# primary_decoupling.net
KiCad netlist of a schematic drawn in Altium Designer
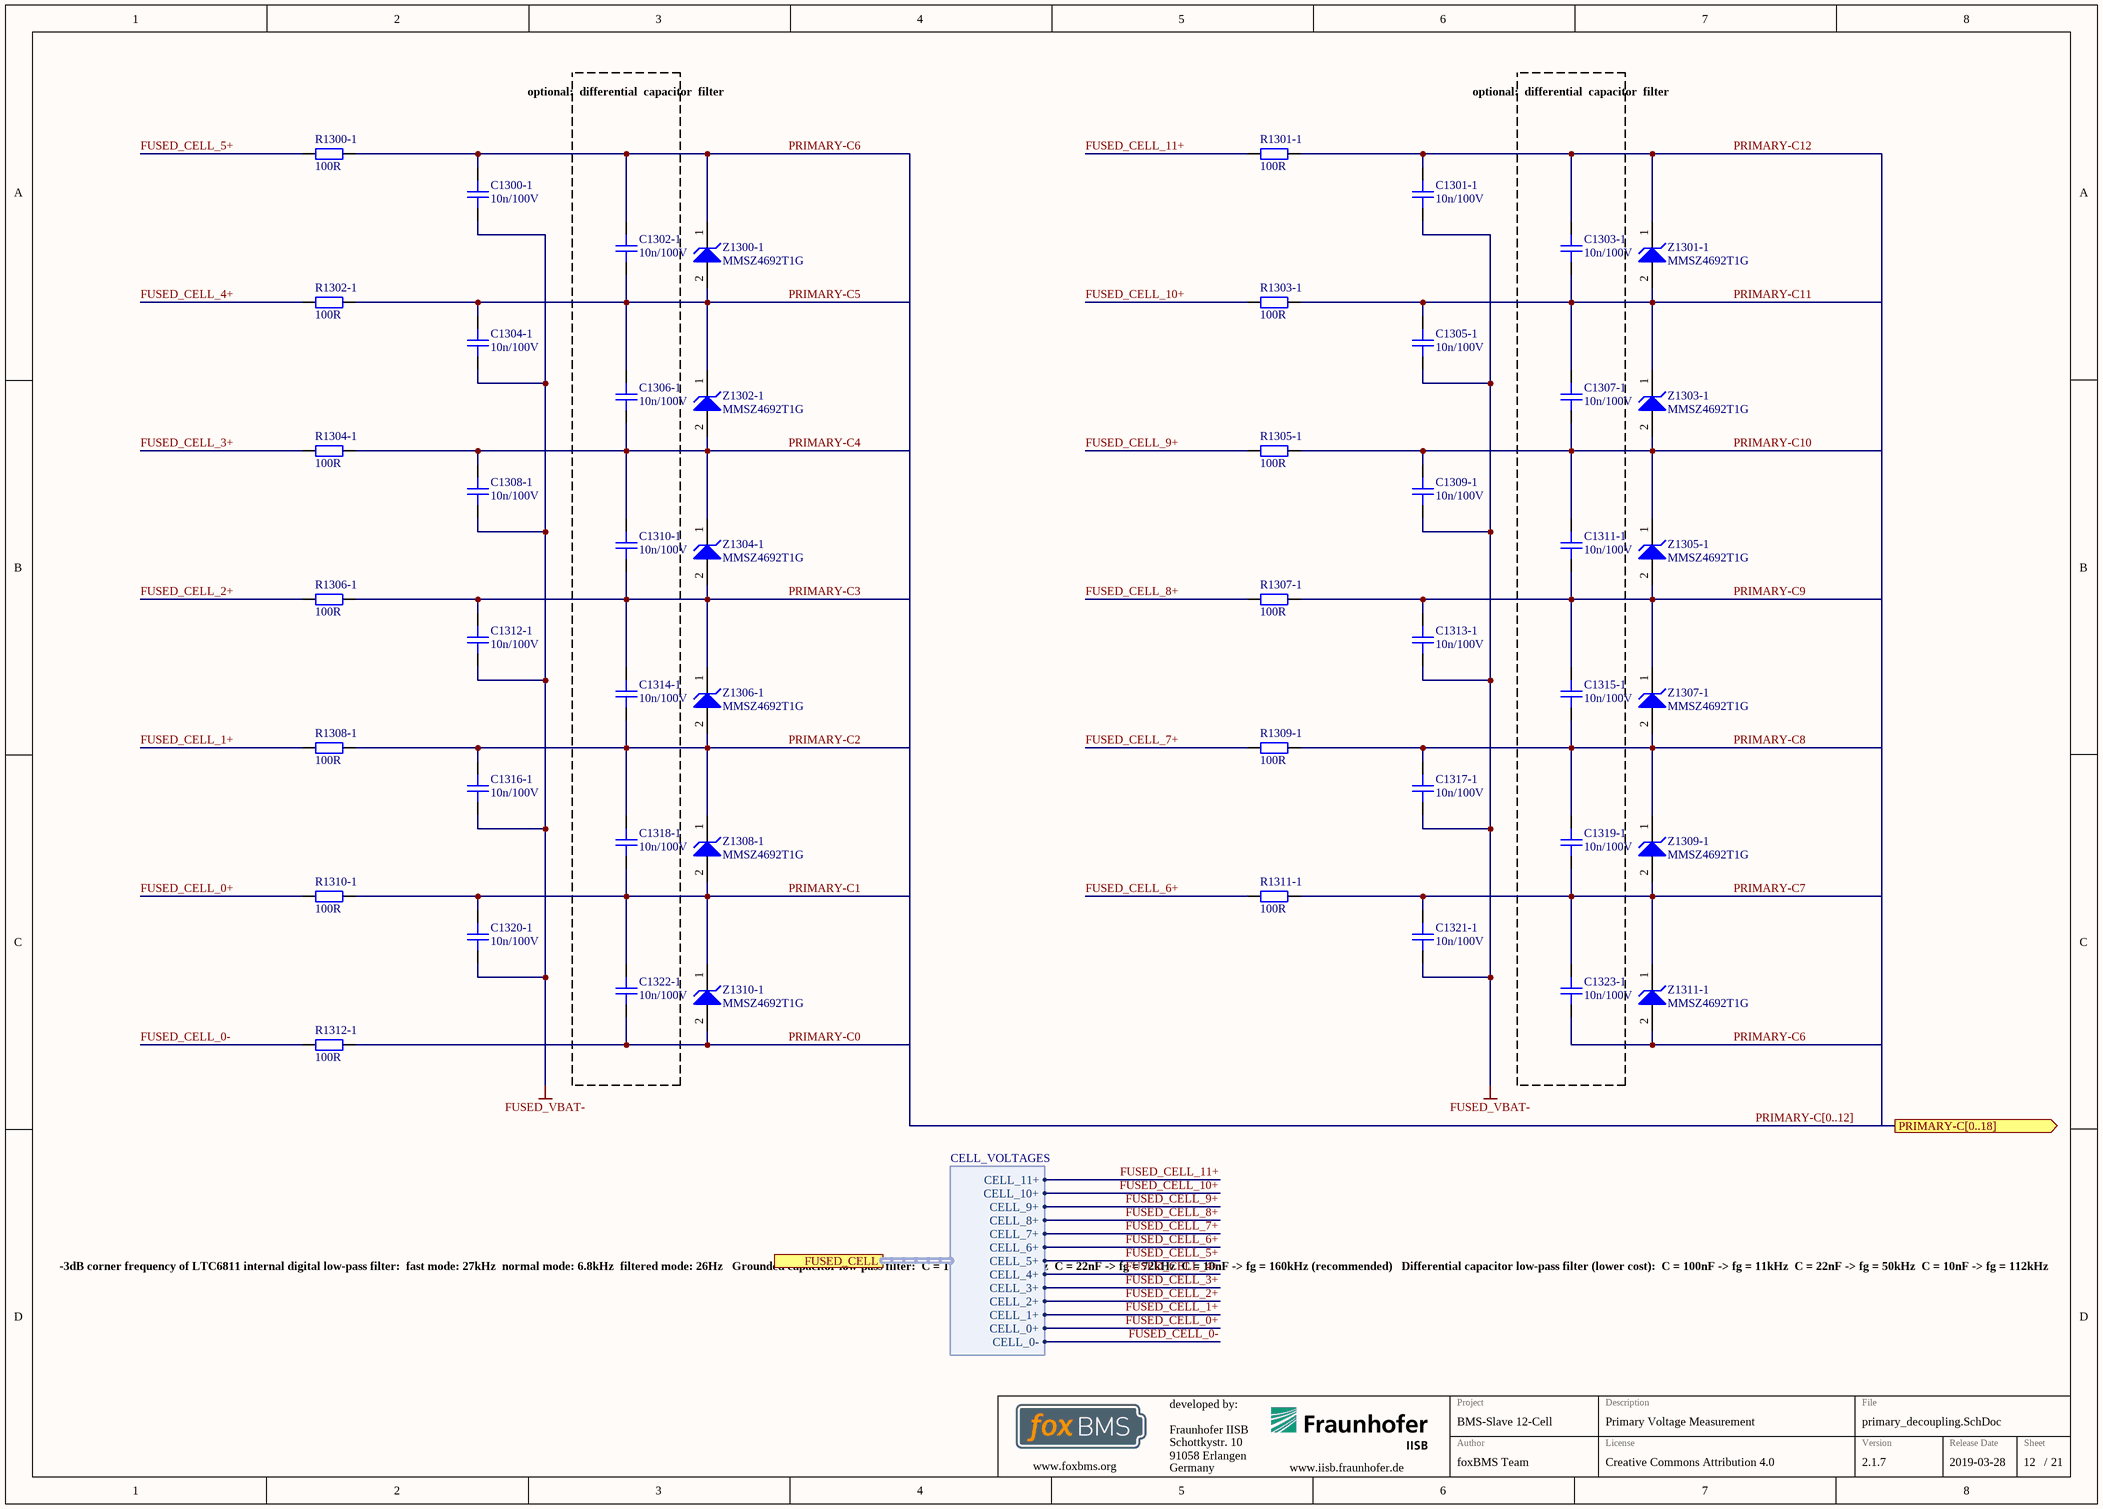
[diagram p0: primary_decoupling.SchDoc]

(export (version "E")
  (design (tool "Eeschema 10.0.6"))
  (components
    (comp (ref "C1300-1")
      (value "10n/100V")
      (footprint "CAPC1608X08N")
      (description "MLCC")
      (fields (field (name "PART NUMBER") "gen_C_ceramic_10n_100V_X7R_0603"))
      (libsource (lib "OE750") (part "C"))
    )
    (comp (ref "C1301-1")
      (value "10n/100V")
      (footprint "CAPC1608X08N")
      (description "MLCC")
      (fields (field (name "PART NUMBER") "gen_C_ceramic_10n_100V_X7R_0603"))
      (libsource (lib "OE750") (part "C"))
    )
    (comp (ref "C1302-1")
      (value "10n/100V")
      (footprint "CAPC1608X08N")
      (description "MLCC")
      (fields (field (name "PART NUMBER") "gen_C_ceramic_10n_100V_X7R_0603"))
      (libsource (lib "OE750") (part "C"))
    )
    (comp (ref "C1303-1")
      (value "10n/100V")
      (footprint "CAPC1608X08N")
      (description "MLCC")
      (fields (field (name "PART NUMBER") "gen_C_ceramic_10n_100V_X7R_0603"))
      (libsource (lib "OE750") (part "C"))
    )
    (comp (ref "C1304-1")
      (value "10n/100V")
      (footprint "CAPC1608X08N")
      (description "MLCC")
      (fields (field (name "PART NUMBER") "gen_C_ceramic_10n_100V_X7R_0603"))
      (libsource (lib "OE750") (part "C"))
    )
    (comp (ref "C1305-1")
      (value "10n/100V")
      (footprint "CAPC1608X08N")
      (description "MLCC")
      (fields (field (name "PART NUMBER") "gen_C_ceramic_10n_100V_X7R_0603"))
      (libsource (lib "OE750") (part "C"))
    )
    (comp (ref "C1306-1")
      (value "10n/100V")
      (footprint "CAPC1608X08N")
      (description "MLCC")
      (fields (field (name "PART NUMBER") "gen_C_ceramic_10n_100V_X7R_0603"))
      (libsource (lib "OE750") (part "C"))
    )
    (comp (ref "C1307-1")
      (value "10n/100V")
      (footprint "CAPC1608X08N")
      (description "MLCC")
      (fields (field (name "PART NUMBER") "gen_C_ceramic_10n_100V_X7R_0603"))
      (libsource (lib "OE750") (part "C"))
    )
    (comp (ref "C1308-1")
      (value "10n/100V")
      (footprint "CAPC1608X08N")
      (description "MLCC")
      (fields (field (name "PART NUMBER") "gen_C_ceramic_10n_100V_X7R_0603"))
      (libsource (lib "OE750") (part "C"))
    )
    (comp (ref "C1309-1")
      (value "10n/100V")
      (footprint "CAPC1608X08N")
      (description "MLCC")
      (fields (field (name "PART NUMBER") "gen_C_ceramic_10n_100V_X7R_0603"))
      (libsource (lib "OE750") (part "C"))
    )
    (comp (ref "C1310-1")
      (value "10n/100V")
      (footprint "CAPC1608X08N")
      (description "MLCC")
      (fields (field (name "PART NUMBER") "gen_C_ceramic_10n_100V_X7R_0603"))
      (libsource (lib "OE750") (part "C"))
    )
    (comp (ref "C1311-1")
      (value "10n/100V")
      (footprint "CAPC1608X08N")
      (description "MLCC")
      (fields (field (name "PART NUMBER") "gen_C_ceramic_10n_100V_X7R_0603"))
      (libsource (lib "OE750") (part "C"))
    )
    (comp (ref "C1312-1")
      (value "10n/100V")
      (footprint "CAPC1608X08N")
      (description "MLCC")
      (fields (field (name "PART NUMBER") "gen_C_ceramic_10n_100V_X7R_0603"))
      (libsource (lib "OE750") (part "C"))
    )
    (comp (ref "C1313-1")
      (value "10n/100V")
      (footprint "CAPC1608X08N")
      (description "MLCC")
      (fields (field (name "PART NUMBER") "gen_C_ceramic_10n_100V_X7R_0603"))
      (libsource (lib "OE750") (part "C"))
    )
    (comp (ref "C1314-1")
      (value "10n/100V")
      (footprint "CAPC1608X08N")
      (description "MLCC")
      (fields (field (name "PART NUMBER") "gen_C_ceramic_10n_100V_X7R_0603"))
      (libsource (lib "OE750") (part "C"))
    )
    (comp (ref "C1315-1")
      (value "10n/100V")
      (footprint "CAPC1608X08N")
      (description "MLCC")
      (fields (field (name "PART NUMBER") "gen_C_ceramic_10n_100V_X7R_0603"))
      (libsource (lib "OE750") (part "C"))
    )
    (comp (ref "C1316-1")
      (value "10n/100V")
      (footprint "CAPC1608X08N")
      (description "MLCC")
      (fields (field (name "PART NUMBER") "gen_C_ceramic_10n_100V_X7R_0603"))
      (libsource (lib "OE750") (part "C"))
    )
    (comp (ref "C1317-1")
      (value "10n/100V")
      (footprint "CAPC1608X08N")
      (description "MLCC")
      (fields (field (name "PART NUMBER") "gen_C_ceramic_10n_100V_X7R_0603"))
      (libsource (lib "OE750") (part "C"))
    )
    (comp (ref "C1318-1")
      (value "10n/100V")
      (footprint "CAPC1608X08N")
      (description "MLCC")
      (fields (field (name "PART NUMBER") "gen_C_ceramic_10n_100V_X7R_0603"))
      (libsource (lib "OE750") (part "C"))
    )
    (comp (ref "C1319-1")
      (value "10n/100V")
      (footprint "CAPC1608X08N")
      (description "MLCC")
      (fields (field (name "PART NUMBER") "gen_C_ceramic_10n_100V_X7R_0603"))
      (libsource (lib "OE750") (part "C"))
    )
    (comp (ref "C1320-1")
      (value "10n/100V")
      (footprint "CAPC1608X08N")
      (description "MLCC")
      (fields (field (name "PART NUMBER") "gen_C_ceramic_10n_100V_X7R_0603"))
      (libsource (lib "OE750") (part "C"))
    )
    (comp (ref "C1321-1")
      (value "10n/100V")
      (footprint "CAPC1608X08N")
      (description "MLCC")
      (fields (field (name "PART NUMBER") "gen_C_ceramic_10n_100V_X7R_0603"))
      (libsource (lib "OE750") (part "C"))
    )
    (comp (ref "C1322-1")
      (value "10n/100V")
      (footprint "CAPC1608X08N")
      (description "MLCC")
      (fields (field (name "PART NUMBER") "gen_C_ceramic_10n_100V_X7R_0603"))
      (libsource (lib "OE750") (part "C"))
    )
    (comp (ref "C1323-1")
      (value "10n/100V")
      (footprint "CAPC1608X08N")
      (description "MLCC")
      (fields (field (name "PART NUMBER") "gen_C_ceramic_10n_100V_X7R_0603"))
      (libsource (lib "OE750") (part "C"))
    )
    (comp (ref "R1300-1")
      (value "100R")
      (footprint "RESC1608X05N")
      (description "SMD Resistor 100R 0603")
      (fields (field (name "PART NUMBER") "gen_R_100R_0603") (field (name "TOLERANCE") "1%"))
      (libsource (lib "OE750") (part "R"))
    )
    (comp (ref "R1301-1")
      (value "100R")
      (footprint "RESC1608X05N")
      (description "SMD Resistor 100R 0603")
      (fields (field (name "PART NUMBER") "gen_R_100R_0603") (field (name "TOLERANCE") "1%"))
      (libsource (lib "OE750") (part "R"))
    )
    (comp (ref "R1302-1")
      (value "100R")
      (footprint "RESC1608X05N")
      (description "SMD Resistor 100R 0603")
      (fields (field (name "PART NUMBER") "gen_R_100R_0603") (field (name "TOLERANCE") "1%"))
      (libsource (lib "OE750") (part "R"))
    )
    (comp (ref "R1303-1")
      (value "100R")
      (footprint "RESC1608X05N")
      (description "SMD Resistor 100R 0603")
      (fields (field (name "PART NUMBER") "gen_R_100R_0603") (field (name "TOLERANCE") "1%"))
      (libsource (lib "OE750") (part "R"))
    )
    (comp (ref "R1304-1")
      (value "100R")
      (footprint "RESC1608X05N")
      (description "SMD Resistor 100R 0603")
      (fields (field (name "PART NUMBER") "gen_R_100R_0603") (field (name "TOLERANCE") "1%"))
      (libsource (lib "OE750") (part "R"))
    )
    (comp (ref "R1305-1")
      (value "100R")
      (footprint "RESC1608X05N")
      (description "SMD Resistor 100R 0603")
      (fields (field (name "PART NUMBER") "gen_R_100R_0603") (field (name "TOLERANCE") "1%"))
      (libsource (lib "OE750") (part "R"))
    )
    (comp (ref "R1306-1")
      (value "100R")
      (footprint "RESC1608X05N")
      (description "SMD Resistor 100R 0603")
      (fields (field (name "PART NUMBER") "gen_R_100R_0603") (field (name "TOLERANCE") "1%"))
      (libsource (lib "OE750") (part "R"))
    )
    (comp (ref "R1307-1")
      (value "100R")
      (footprint "RESC1608X05N")
      (description "SMD Resistor 100R 0603")
      (fields (field (name "PART NUMBER") "gen_R_100R_0603") (field (name "TOLERANCE") "1%"))
      (libsource (lib "OE750") (part "R"))
    )
    (comp (ref "R1308-1")
      (value "100R")
      (footprint "RESC1608X05N")
      (description "SMD Resistor 100R 0603")
      (fields (field (name "PART NUMBER") "gen_R_100R_0603") (field (name "TOLERANCE") "1%"))
      (libsource (lib "OE750") (part "R"))
    )
    (comp (ref "R1309-1")
      (value "100R")
      (footprint "RESC1608X05N")
      (description "SMD Resistor 100R 0603")
      (fields (field (name "PART NUMBER") "gen_R_100R_0603") (field (name "TOLERANCE") "1%"))
      (libsource (lib "OE750") (part "R"))
    )
    (comp (ref "R1310-1")
      (value "100R")
      (footprint "RESC1608X05N")
      (description "SMD Resistor 100R 0603")
      (fields (field (name "PART NUMBER") "gen_R_100R_0603") (field (name "TOLERANCE") "1%"))
      (libsource (lib "OE750") (part "R"))
    )
    (comp (ref "R1311-1")
      (value "100R")
      (footprint "RESC1608X05N")
      (description "SMD Resistor 100R 0603")
      (fields (field (name "PART NUMBER") "gen_R_100R_0603") (field (name "TOLERANCE") "1%"))
      (libsource (lib "OE750") (part "R"))
    )
    (comp (ref "R1312-1")
      (value "100R")
      (footprint "RESC1608X05N")
      (description "SMD Resistor 100R 0603")
      (fields (field (name "PART NUMBER") "gen_R_100R_0603") (field (name "TOLERANCE") "1%"))
      (libsource (lib "OE750") (part "R"))
    )
    (comp (ref "Z1300-1")
      (value "MMSZ4692T1G")
      (footprint "ONSC-SOD-123-2-425-04_V")
      (description "Zener Voltage Regulator, 500 mW, 2-Pin SOD-123, Pb-Free, Tape and Reel")
      (fields (field (name "MANUFACTURER") "On Semiconductor"))
      (libsource (lib "Altium Content Vault") (part "ONSC-K1A2-2"))
    )
    (comp (ref "Z1301-1")
      (value "MMSZ4692T1G")
      (footprint "ONSC-SOD-123-2-425-04_V")
      (description "Zener Voltage Regulator, 500 mW, 2-Pin SOD-123, Pb-Free, Tape and Reel")
      (fields (field (name "MANUFACTURER") "On Semiconductor"))
      (libsource (lib "Altium Content Vault") (part "ONSC-K1A2-2"))
    )
    (comp (ref "Z1302-1")
      (value "MMSZ4692T1G")
      (footprint "ONSC-SOD-123-2-425-04_V")
      (description "Zener Voltage Regulator, 500 mW, 2-Pin SOD-123, Pb-Free, Tape and Reel")
      (fields (field (name "MANUFACTURER") "On Semiconductor"))
      (libsource (lib "Altium Content Vault") (part "ONSC-K1A2-2"))
    )
    (comp (ref "Z1303-1")
      (value "MMSZ4692T1G")
      (footprint "ONSC-SOD-123-2-425-04_V")
      (description "Zener Voltage Regulator, 500 mW, 2-Pin SOD-123, Pb-Free, Tape and Reel")
      (fields (field (name "MANUFACTURER") "On Semiconductor"))
      (libsource (lib "Altium Content Vault") (part "ONSC-K1A2-2"))
    )
    (comp (ref "Z1304-1")
      (value "MMSZ4692T1G")
      (footprint "ONSC-SOD-123-2-425-04_V")
      (description "Zener Voltage Regulator, 500 mW, 2-Pin SOD-123, Pb-Free, Tape and Reel")
      (fields (field (name "MANUFACTURER") "On Semiconductor"))
      (libsource (lib "Altium Content Vault") (part "ONSC-K1A2-2"))
    )
    (comp (ref "Z1305-1")
      (value "MMSZ4692T1G")
      (footprint "ONSC-SOD-123-2-425-04_V")
      (description "Zener Voltage Regulator, 500 mW, 2-Pin SOD-123, Pb-Free, Tape and Reel")
      (fields (field (name "MANUFACTURER") "On Semiconductor"))
      (libsource (lib "Altium Content Vault") (part "ONSC-K1A2-2"))
    )
    (comp (ref "Z1306-1")
      (value "MMSZ4692T1G")
      (footprint "ONSC-SOD-123-2-425-04_V")
      (description "Zener Voltage Regulator, 500 mW, 2-Pin SOD-123, Pb-Free, Tape and Reel")
      (fields (field (name "MANUFACTURER") "On Semiconductor"))
      (libsource (lib "Altium Content Vault") (part "ONSC-K1A2-2"))
    )
    (comp (ref "Z1307-1")
      (value "MMSZ4692T1G")
      (footprint "ONSC-SOD-123-2-425-04_V")
      (description "Zener Voltage Regulator, 500 mW, 2-Pin SOD-123, Pb-Free, Tape and Reel")
      (fields (field (name "MANUFACTURER") "On Semiconductor"))
      (libsource (lib "Altium Content Vault") (part "ONSC-K1A2-2"))
    )
    (comp (ref "Z1308-1")
      (value "MMSZ4692T1G")
      (footprint "ONSC-SOD-123-2-425-04_V")
      (description "Zener Voltage Regulator, 500 mW, 2-Pin SOD-123, Pb-Free, Tape and Reel")
      (fields (field (name "MANUFACTURER") "On Semiconductor"))
      (libsource (lib "Altium Content Vault") (part "ONSC-K1A2-2"))
    )
    (comp (ref "Z1309-1")
      (value "MMSZ4692T1G")
      (footprint "ONSC-SOD-123-2-425-04_V")
      (description "Zener Voltage Regulator, 500 mW, 2-Pin SOD-123, Pb-Free, Tape and Reel")
      (fields (field (name "MANUFACTURER") "On Semiconductor"))
      (libsource (lib "Altium Content Vault") (part "ONSC-K1A2-2"))
    )
    (comp (ref "Z1310-1")
      (value "MMSZ4692T1G")
      (footprint "ONSC-SOD-123-2-425-04_V")
      (description "Zener Voltage Regulator, 500 mW, 2-Pin SOD-123, Pb-Free, Tape and Reel")
      (fields (field (name "MANUFACTURER") "On Semiconductor"))
      (libsource (lib "Altium Content Vault") (part "ONSC-K1A2-2"))
    )
    (comp (ref "Z1311-1")
      (value "MMSZ4692T1G")
      (footprint "ONSC-SOD-123-2-425-04_V")
      (description "Zener Voltage Regulator, 500 mW, 2-Pin SOD-123, Pb-Free, Tape and Reel")
      (fields (field (name "MANUFACTURER") "On Semiconductor"))
      (libsource (lib "Altium Content Vault") (part "ONSC-K1A2-2"))
    )
  )
  (nets
    (net (code "2") (name "/FUSED_CELL_0+") (class "Default")
      (node (ref "R1310-1") (pin "1") (pinfunction "1_1") (pintype "passive"))
    )
    (net (code "3") (name "/FUSED_CELL_0-") (class "Default")
      (node (ref "R1312-1") (pin "1") (pinfunction "1_1") (pintype "passive"))
    )
    (net (code "4") (name "/FUSED_CELL_1+") (class "Default")
      (node (ref "R1308-1") (pin "1") (pinfunction "1_1") (pintype "passive"))
    )
    (net (code "5") (name "/FUSED_CELL_2+") (class "Default")
      (node (ref "R1306-1") (pin "1") (pinfunction "1_1") (pintype "passive"))
    )
    (net (code "6") (name "/FUSED_CELL_3+") (class "Default")
      (node (ref "R1304-1") (pin "1") (pinfunction "1_1") (pintype "passive"))
    )
    (net (code "7") (name "/FUSED_CELL_4+") (class "Default")
      (node (ref "R1302-1") (pin "1") (pinfunction "1_1") (pintype "passive"))
    )
    (net (code "8") (name "/FUSED_CELL_5+") (class "Default")
      (node (ref "R1300-1") (pin "1") (pinfunction "1_1") (pintype "passive"))
    )
    (net (code "9") (name "/FUSED_CELL_6+") (class "Default")
      (node (ref "R1311-1") (pin "1") (pinfunction "1_1") (pintype "passive"))
    )
    (net (code "10") (name "/FUSED_CELL_7+") (class "Default")
      (node (ref "R1309-1") (pin "1") (pinfunction "1_1") (pintype "passive"))
    )
    (net (code "11") (name "/FUSED_CELL_8+") (class "Default")
      (node (ref "R1307-1") (pin "1") (pinfunction "1_1") (pintype "passive"))
    )
    (net (code "12") (name "/FUSED_CELL_9+") (class "Default")
      (node (ref "R1305-1") (pin "1") (pinfunction "1_1") (pintype "passive"))
    )
    (net (code "13") (name "/FUSED_CELL_10+") (class "Default")
      (node (ref "R1303-1") (pin "1") (pinfunction "1_1") (pintype "passive"))
    )
    (net (code "14") (name "/FUSED_CELL_11+") (class "Default")
      (node (ref "R1301-1") (pin "1") (pinfunction "1_1") (pintype "passive"))
    )
    (net (code "15") (name "/PRIMARY-C0") (class "Default")
      (node (ref "C1322-1") (pin "2") (pinfunction "2_2") (pintype "passive"))
      (node (ref "R1312-1") (pin "2") (pinfunction "2_2") (pintype "passive"))
      (node (ref "Z1310-1") (pin "2") (pinfunction "A_2") (pintype "passive"))
    )
    (net (code "16") (name "/PRIMARY-C1") (class "Default")
      (node (ref "C1318-1") (pin "2") (pinfunction "2_2") (pintype "passive"))
      (node (ref "C1320-1") (pin "1") (pinfunction "1_1") (pintype "passive"))
      (node (ref "C1322-1") (pin "1") (pinfunction "1_1") (pintype "passive"))
      (node (ref "R1310-1") (pin "2") (pinfunction "2_2") (pintype "passive"))
      (node (ref "Z1308-1") (pin "2") (pinfunction "A_2") (pintype "passive"))
      (node (ref "Z1310-1") (pin "1") (pinfunction "K_1") (pintype "passive"))
    )
    (net (code "17") (name "/PRIMARY-C2") (class "Default")
      (node (ref "C1314-1") (pin "2") (pinfunction "2_2") (pintype "passive"))
      (node (ref "C1316-1") (pin "1") (pinfunction "1_1") (pintype "passive"))
      (node (ref "C1318-1") (pin "1") (pinfunction "1_1") (pintype "passive"))
      (node (ref "R1308-1") (pin "2") (pinfunction "2_2") (pintype "passive"))
      (node (ref "Z1306-1") (pin "2") (pinfunction "A_2") (pintype "passive"))
      (node (ref "Z1308-1") (pin "1") (pinfunction "K_1") (pintype "passive"))
    )
    (net (code "18") (name "/PRIMARY-C3") (class "Default")
      (node (ref "C1310-1") (pin "2") (pinfunction "2_2") (pintype "passive"))
      (node (ref "C1312-1") (pin "1") (pinfunction "1_1") (pintype "passive"))
      (node (ref "C1314-1") (pin "1") (pinfunction "1_1") (pintype "passive"))
      (node (ref "R1306-1") (pin "2") (pinfunction "2_2") (pintype "passive"))
      (node (ref "Z1304-1") (pin "2") (pinfunction "A_2") (pintype "passive"))
      (node (ref "Z1306-1") (pin "1") (pinfunction "K_1") (pintype "passive"))
    )
    (net (code "19") (name "/PRIMARY-C4") (class "Default")
      (node (ref "C1306-1") (pin "2") (pinfunction "2_2") (pintype "passive"))
      (node (ref "C1308-1") (pin "1") (pinfunction "1_1") (pintype "passive"))
      (node (ref "C1310-1") (pin "1") (pinfunction "1_1") (pintype "passive"))
      (node (ref "R1304-1") (pin "2") (pinfunction "2_2") (pintype "passive"))
      (node (ref "Z1302-1") (pin "2") (pinfunction "A_2") (pintype "passive"))
      (node (ref "Z1304-1") (pin "1") (pinfunction "K_1") (pintype "passive"))
    )
    (net (code "20") (name "/PRIMARY-C5") (class "Default")
      (node (ref "C1302-1") (pin "2") (pinfunction "2_2") (pintype "passive"))
      (node (ref "C1304-1") (pin "1") (pinfunction "1_1") (pintype "passive"))
      (node (ref "C1306-1") (pin "1") (pinfunction "1_1") (pintype "passive"))
      (node (ref "R1302-1") (pin "2") (pinfunction "2_2") (pintype "passive"))
      (node (ref "Z1300-1") (pin "2") (pinfunction "A_2") (pintype "passive"))
      (node (ref "Z1302-1") (pin "1") (pinfunction "K_1") (pintype "passive"))
    )
    (net (code "21") (name "/PRIMARY-C6") (class "Default")
      (node (ref "C1300-1") (pin "1") (pinfunction "1_1") (pintype "passive"))
      (node (ref "C1302-1") (pin "1") (pinfunction "1_1") (pintype "passive"))
      (node (ref "C1323-1") (pin "2") (pinfunction "2_2") (pintype "passive"))
      (node (ref "R1300-1") (pin "2") (pinfunction "2_2") (pintype "passive"))
      (node (ref "Z1300-1") (pin "1") (pinfunction "K_1") (pintype "passive"))
      (node (ref "Z1311-1") (pin "2") (pinfunction "A_2") (pintype "passive"))
    )
    (net (code "22") (name "/PRIMARY-C7") (class "Default")
      (node (ref "C1319-1") (pin "2") (pinfunction "2_2") (pintype "passive"))
      (node (ref "C1321-1") (pin "1") (pinfunction "1_1") (pintype "passive"))
      (node (ref "C1323-1") (pin "1") (pinfunction "1_1") (pintype "passive"))
      (node (ref "R1311-1") (pin "2") (pinfunction "2_2") (pintype "passive"))
      (node (ref "Z1309-1") (pin "2") (pinfunction "A_2") (pintype "passive"))
      (node (ref "Z1311-1") (pin "1") (pinfunction "K_1") (pintype "passive"))
    )
    (net (code "23") (name "/PRIMARY-C8") (class "Default")
      (node (ref "C1315-1") (pin "2") (pinfunction "2_2") (pintype "passive"))
      (node (ref "C1317-1") (pin "1") (pinfunction "1_1") (pintype "passive"))
      (node (ref "C1319-1") (pin "1") (pinfunction "1_1") (pintype "passive"))
      (node (ref "R1309-1") (pin "2") (pinfunction "2_2") (pintype "passive"))
      (node (ref "Z1307-1") (pin "2") (pinfunction "A_2") (pintype "passive"))
      (node (ref "Z1309-1") (pin "1") (pinfunction "K_1") (pintype "passive"))
    )
    (net (code "24") (name "/PRIMARY-C9") (class "Default")
      (node (ref "C1311-1") (pin "2") (pinfunction "2_2") (pintype "passive"))
      (node (ref "C1313-1") (pin "1") (pinfunction "1_1") (pintype "passive"))
      (node (ref "C1315-1") (pin "1") (pinfunction "1_1") (pintype "passive"))
      (node (ref "R1307-1") (pin "2") (pinfunction "2_2") (pintype "passive"))
      (node (ref "Z1305-1") (pin "2") (pinfunction "A_2") (pintype "passive"))
      (node (ref "Z1307-1") (pin "1") (pinfunction "K_1") (pintype "passive"))
    )
    (net (code "25") (name "/PRIMARY-C10") (class "Default")
      (node (ref "C1307-1") (pin "2") (pinfunction "2_2") (pintype "passive"))
      (node (ref "C1309-1") (pin "1") (pinfunction "1_1") (pintype "passive"))
      (node (ref "C1311-1") (pin "1") (pinfunction "1_1") (pintype "passive"))
      (node (ref "R1305-1") (pin "2") (pinfunction "2_2") (pintype "passive"))
      (node (ref "Z1303-1") (pin "2") (pinfunction "A_2") (pintype "passive"))
      (node (ref "Z1305-1") (pin "1") (pinfunction "K_1") (pintype "passive"))
    )
    (net (code "26") (name "/PRIMARY-C11") (class "Default")
      (node (ref "C1303-1") (pin "2") (pinfunction "2_2") (pintype "passive"))
      (node (ref "C1305-1") (pin "1") (pinfunction "1_1") (pintype "passive"))
      (node (ref "C1307-1") (pin "1") (pinfunction "1_1") (pintype "passive"))
      (node (ref "R1303-1") (pin "2") (pinfunction "2_2") (pintype "passive"))
      (node (ref "Z1301-1") (pin "2") (pinfunction "A_2") (pintype "passive"))
      (node (ref "Z1303-1") (pin "1") (pinfunction "K_1") (pintype "passive"))
    )
    (net (code "27") (name "/PRIMARY-C12") (class "Default")
      (node (ref "C1301-1") (pin "1") (pinfunction "1_1") (pintype "passive"))
      (node (ref "C1303-1") (pin "1") (pinfunction "1_1") (pintype "passive"))
      (node (ref "R1301-1") (pin "2") (pinfunction "2_2") (pintype "passive"))
      (node (ref "Z1301-1") (pin "1") (pinfunction "K_1") (pintype "passive"))
    )
    (net (code "30") (name "FUSED_VBAT-") (class "Default")
      (node (ref "C1300-1") (pin "2") (pinfunction "2_2") (pintype "passive"))
      (node (ref "C1301-1") (pin "2") (pinfunction "2_2") (pintype "passive"))
      (node (ref "C1304-1") (pin "2") (pinfunction "2_2") (pintype "passive"))
      (node (ref "C1305-1") (pin "2") (pinfunction "2_2") (pintype "passive"))
      (node (ref "C1308-1") (pin "2") (pinfunction "2_2") (pintype "passive"))
      (node (ref "C1309-1") (pin "2") (pinfunction "2_2") (pintype "passive"))
      (node (ref "C1312-1") (pin "2") (pinfunction "2_2") (pintype "passive"))
      (node (ref "C1313-1") (pin "2") (pinfunction "2_2") (pintype "passive"))
      (node (ref "C1316-1") (pin "2") (pinfunction "2_2") (pintype "passive"))
      (node (ref "C1317-1") (pin "2") (pinfunction "2_2") (pintype "passive"))
      (node (ref "C1320-1") (pin "2") (pinfunction "2_2") (pintype "passive"))
      (node (ref "C1321-1") (pin "2") (pinfunction "2_2") (pintype "passive"))
    )
  )
)
